# LV8731.net
KiCad netlist of a schematic drawn in Altium Designer
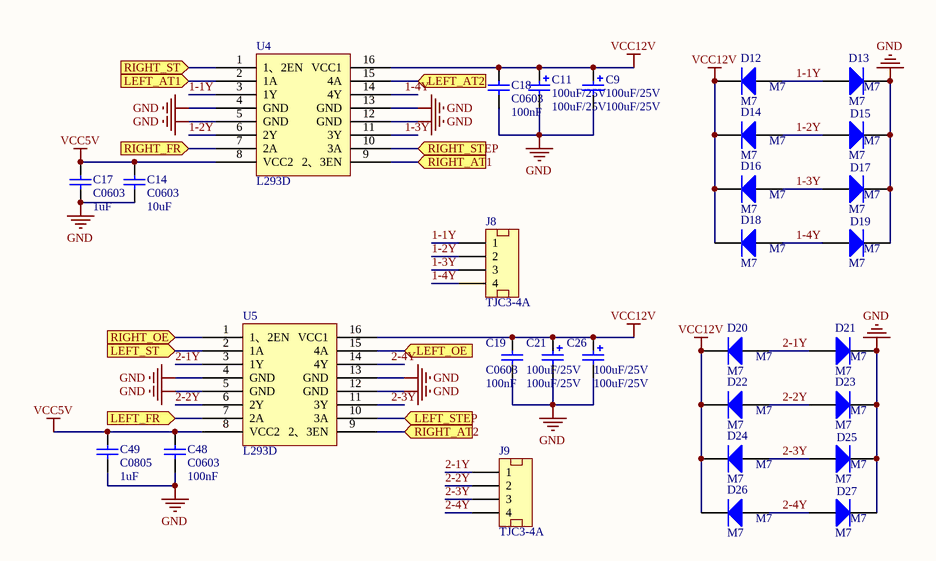
[diagram p0: LV8731.SchDoc]

(export (version "E")
  (design (tool "Eeschema 10.0.6"))
  (components
    (comp (ref "C9")
      (value "100uF/25V")
      (footprint "16V220uF")
      (description "Polarized Capacitor (Surface Mount)")
      (fields (field (name "ALTIUM_VALUE") "100uF/25V"))
      (libsource (lib "schumyhao's_Device") (part "Cap Pol3"))
    )
    (comp (ref "C11")
      (value "100uF/25V")
      (footprint "16V220uF")
      (description "Polarized Capacitor (Surface Mount)")
      (fields (field (name "ALTIUM_VALUE") "100uF/25V"))
      (libsource (lib "schumyhao's_Device") (part "Cap Pol3"))
    )
    (comp (ref "C14")
      (value "C0603")
      (footprint "C0603")
      (description "Capacitor (Semiconductor SIM Model)")
      (fields (field (name "ALTIUM_VALUE") "10uF"))
      (libsource (lib "schumyhao's_Device") (part "Cap Semi"))
    )
    (comp (ref "C17")
      (value "C0603")
      (footprint "C0805")
      (description "Capacitor (Semiconductor SIM Model)")
      (fields (field (name "ALTIUM_VALUE") "1uF"))
      (libsource (lib "schumyhao's_Device") (part "Cap Semi"))
    )
    (comp (ref "C18")
      (value "C0603")
      (footprint "C0603")
      (description "Capacitor (Semiconductor SIM Model)")
      (fields (field (name "ALTIUM_VALUE") "100nF"))
      (libsource (lib "schumyhao's_Device") (part "Cap Semi"))
    )
    (comp (ref "C19")
      (value "C0603")
      (footprint "C0603")
      (description "Capacitor (Semiconductor SIM Model)")
      (fields (field (name "ALTIUM_VALUE") "100nF"))
      (libsource (lib "schumyhao's_Device") (part "Cap Semi"))
    )
    (comp (ref "C21")
      (value "100uF/25V")
      (footprint "16V220uF")
      (description "Polarized Capacitor (Surface Mount)")
      (fields (field (name "ALTIUM_VALUE") "100uF/25V"))
      (libsource (lib "schumyhao's_Device") (part "Cap Pol3"))
    )
    (comp (ref "C26")
      (value "100uF/25V")
      (footprint "16V220uF")
      (description "Polarized Capacitor (Surface Mount)")
      (fields (field (name "ALTIUM_VALUE") "100uF/25V"))
      (libsource (lib "schumyhao's_Device") (part "Cap Pol3"))
    )
    (comp (ref "C48")
      (value "C0603")
      (footprint "C0603")
      (description "Capacitor (Semiconductor SIM Model)")
      (fields (field (name "ALTIUM_VALUE") "100nF"))
      (libsource (lib "schumyhao's_Device") (part "Cap Semi"))
    )
    (comp (ref "C49")
      (value "C0805")
      (footprint "C0805")
      (description "Capacitor (Semiconductor SIM Model)")
      (fields (field (name "ALTIUM_VALUE") "1uF"))
      (libsource (lib "schumyhao's_Device") (part "Cap Semi"))
    )
    (comp (ref "D12")
      (value "M7")
      (footprint "403D_02")
      (description "Default Diode")
      (fields (field (name "ALTIUM_VALUE") "M7") (field (name "PUBLISHER") "Altium Limited"))
      (libsource (lib "Miscellaneous Devices") (part "Diode"))
    )
    (comp (ref "D13")
      (value "M7")
      (footprint "403D_02")
      (description "Default Diode")
      (fields (field (name "ALTIUM_VALUE") "M7") (field (name "PUBLISHER") "Altium Limited"))
      (libsource (lib "Miscellaneous Devices") (part "Diode"))
    )
    (comp (ref "D14")
      (value "M7")
      (footprint "403D_02")
      (description "Default Diode")
      (fields (field (name "ALTIUM_VALUE") "M7") (field (name "PUBLISHER") "Altium Limited"))
      (libsource (lib "Miscellaneous Devices") (part "Diode"))
    )
    (comp (ref "D15")
      (value "M7")
      (footprint "403D_02")
      (description "Default Diode")
      (fields (field (name "ALTIUM_VALUE") "M7") (field (name "PUBLISHER") "Altium Limited"))
      (libsource (lib "Miscellaneous Devices") (part "Diode"))
    )
    (comp (ref "D16")
      (value "M7")
      (footprint "403D_02")
      (description "Default Diode")
      (fields (field (name "ALTIUM_VALUE") "M7") (field (name "PUBLISHER") "Altium Limited"))
      (libsource (lib "Miscellaneous Devices") (part "Diode"))
    )
    (comp (ref "D17")
      (value "M7")
      (footprint "403D_02")
      (description "Default Diode")
      (fields (field (name "ALTIUM_VALUE") "M7") (field (name "PUBLISHER") "Altium Limited"))
      (libsource (lib "Miscellaneous Devices") (part "Diode"))
    )
    (comp (ref "D18")
      (value "M7")
      (footprint "403D_02")
      (description "Default Diode")
      (fields (field (name "ALTIUM_VALUE") "M7") (field (name "PUBLISHER") "Altium Limited"))
      (libsource (lib "Miscellaneous Devices") (part "Diode"))
    )
    (comp (ref "D19")
      (value "M7")
      (footprint "403D_02")
      (description "Default Diode")
      (fields (field (name "ALTIUM_VALUE") "M7") (field (name "PUBLISHER") "Altium Limited"))
      (libsource (lib "Miscellaneous Devices") (part "Diode"))
    )
    (comp (ref "D20")
      (value "M7")
      (footprint "403D_02")
      (description "Default Diode")
      (fields (field (name "ALTIUM_VALUE") "M7") (field (name "PUBLISHER") "Altium Limited"))
      (libsource (lib "Miscellaneous Devices") (part "Diode"))
    )
    (comp (ref "D21")
      (value "M7")
      (footprint "403D_02")
      (description "Default Diode")
      (fields (field (name "ALTIUM_VALUE") "M7") (field (name "PUBLISHER") "Altium Limited"))
      (libsource (lib "Miscellaneous Devices") (part "Diode"))
    )
    (comp (ref "D22")
      (value "M7")
      (footprint "403D_02")
      (description "Default Diode")
      (fields (field (name "ALTIUM_VALUE") "M7") (field (name "PUBLISHER") "Altium Limited"))
      (libsource (lib "Miscellaneous Devices") (part "Diode"))
    )
    (comp (ref "D23")
      (value "M7")
      (footprint "403D_02")
      (description "Default Diode")
      (fields (field (name "ALTIUM_VALUE") "M7") (field (name "PUBLISHER") "Altium Limited"))
      (libsource (lib "Miscellaneous Devices") (part "Diode"))
    )
    (comp (ref "D24")
      (value "M7")
      (footprint "403D_02")
      (description "Default Diode")
      (fields (field (name "ALTIUM_VALUE") "M7") (field (name "PUBLISHER") "Altium Limited"))
      (libsource (lib "Miscellaneous Devices") (part "Diode"))
    )
    (comp (ref "D25")
      (value "M7")
      (footprint "403D_02")
      (description "Default Diode")
      (fields (field (name "ALTIUM_VALUE") "M7") (field (name "PUBLISHER") "Altium Limited"))
      (libsource (lib "Miscellaneous Devices") (part "Diode"))
    )
    (comp (ref "D26")
      (value "M7")
      (footprint "403D_02")
      (description "Default Diode")
      (fields (field (name "ALTIUM_VALUE") "M7") (field (name "PUBLISHER") "Altium Limited"))
      (libsource (lib "Miscellaneous Devices") (part "Diode"))
    )
    (comp (ref "D27")
      (value "M7")
      (footprint "403D_02")
      (description "Default Diode")
      (fields (field (name "ALTIUM_VALUE") "M7") (field (name "PUBLISHER") "Altium Limited"))
      (libsource (lib "Miscellaneous Devices") (part "Diode"))
    )
    (comp (ref "J8")
      (value "TJC3-4A")
      (footprint "TJC3-4A")
      (fields (field (name "PUBLISHER") "Altium Limited"))
      (libsource (lib "schumyhao's_Device") (part "TJC3-4A"))
    )
    (comp (ref "J9")
      (value "TJC3-4A")
      (footprint "TJC3-4A")
      (fields (field (name "PUBLISHER") "Altium Limited"))
      (libsource (lib "schumyhao's_Device") (part "TJC3-4A"))
    )
    (comp (ref "U4") (value "L293D") (footprint "DIP16") (libsource (lib "schumyhao's_IC") (part "L293D")))
    (comp (ref "U5") (value "L293D") (footprint "DIP16") (libsource (lib "schumyhao's_IC") (part "L293D")))
  )
  (nets
    (net (code "1") (name "/1-1Y") (class "Default")
      (node (ref "D12") (pin "1") (pinfunction "A_1") (pintype "passive"))
      (node (ref "D13") (pin "1") (pinfunction "A_1") (pintype "passive"))
      (node (ref "J8") (pin "1") (pinfunction "1_1") (pintype "passive"))
      (node (ref "U4") (pin "3") (pinfunction "1Y_3") (pintype "passive"))
    )
    (net (code "2") (name "/1-2Y") (class "Default")
      (node (ref "D14") (pin "1") (pinfunction "A_1") (pintype "passive"))
      (node (ref "D15") (pin "1") (pinfunction "A_1") (pintype "passive"))
      (node (ref "J8") (pin "2") (pinfunction "2_2") (pintype "passive"))
      (node (ref "U4") (pin "6") (pinfunction "2Y_6") (pintype "passive"))
    )
    (net (code "3") (name "/1-3Y") (class "Default")
      (node (ref "D16") (pin "1") (pinfunction "A_1") (pintype "passive"))
      (node (ref "D17") (pin "1") (pinfunction "A_1") (pintype "passive"))
      (node (ref "J8") (pin "3") (pinfunction "3_3") (pintype "passive"))
      (node (ref "U4") (pin "11") (pinfunction "3Y_11") (pintype "passive"))
    )
    (net (code "4") (name "/1-4Y") (class "Default")
      (node (ref "D18") (pin "1") (pinfunction "A_1") (pintype "passive"))
      (node (ref "D19") (pin "1") (pinfunction "A_1") (pintype "passive"))
      (node (ref "J8") (pin "4") (pinfunction "4_4") (pintype "passive"))
      (node (ref "U4") (pin "14") (pinfunction "4Y_14") (pintype "passive"))
    )
    (net (code "5") (name "/2-1Y") (class "Default")
      (node (ref "D20") (pin "1") (pinfunction "A_1") (pintype "passive"))
      (node (ref "D21") (pin "1") (pinfunction "A_1") (pintype "passive"))
      (node (ref "J9") (pin "1") (pinfunction "1_1") (pintype "passive"))
      (node (ref "U5") (pin "3") (pinfunction "1Y_3") (pintype "passive"))
    )
    (net (code "6") (name "/2-2Y") (class "Default")
      (node (ref "D22") (pin "1") (pinfunction "A_1") (pintype "passive"))
      (node (ref "D23") (pin "1") (pinfunction "A_1") (pintype "passive"))
      (node (ref "J9") (pin "2") (pinfunction "2_2") (pintype "passive"))
      (node (ref "U5") (pin "6") (pinfunction "2Y_6") (pintype "passive"))
    )
    (net (code "7") (name "/2-3Y") (class "Default")
      (node (ref "D24") (pin "1") (pinfunction "A_1") (pintype "passive"))
      (node (ref "D25") (pin "1") (pinfunction "A_1") (pintype "passive"))
      (node (ref "J9") (pin "3") (pinfunction "3_3") (pintype "passive"))
      (node (ref "U5") (pin "11") (pinfunction "3Y_11") (pintype "passive"))
    )
    (net (code "8") (name "/2-4Y") (class "Default")
      (node (ref "D26") (pin "1") (pinfunction "A_1") (pintype "passive"))
      (node (ref "D27") (pin "1") (pinfunction "A_1") (pintype "passive"))
      (node (ref "J9") (pin "4") (pinfunction "4_4") (pintype "passive"))
      (node (ref "U5") (pin "14") (pinfunction "4Y_14") (pintype "passive"))
    )
    (net (code "9") (name "/LEFT_AT1") (class "Default")
      (node (ref "U4") (pin "2") (pinfunction "1A_2") (pintype "passive"))
    )
    (net (code "10") (name "/LEFT_AT2") (class "Default")
      (node (ref "U4") (pin "15") (pinfunction "4A_15") (pintype "passive"))
    )
    (net (code "11") (name "/LEFT_FR") (class "Default")
      (node (ref "U5") (pin "7") (pinfunction "2A_7") (pintype "passive"))
    )
    (net (code "12") (name "/LEFT_OE") (class "Default")
      (node (ref "U5") (pin "15") (pinfunction "4A_15") (pintype "passive"))
    )
    (net (code "13") (name "/LEFT_ST") (class "Default")
      (node (ref "U5") (pin "2") (pinfunction "1A_2") (pintype "passive"))
    )
    (net (code "14") (name "/LEFT_STEP") (class "Default")
      (node (ref "U5") (pin "10") (pinfunction "3A_10") (pintype "passive"))
    )
    (net (code "15") (name "/RIGHT_AT1") (class "Default")
      (node (ref "U4") (pin "9") (pinfunction "2、3EN_9") (pintype "passive"))
    )
    (net (code "16") (name "/RIGHT_AT2") (class "Default")
      (node (ref "U5") (pin "9") (pinfunction "2、3EN_9") (pintype "passive"))
    )
    (net (code "17") (name "/RIGHT_FR") (class "Default")
      (node (ref "U4") (pin "7") (pinfunction "2A_7") (pintype "passive"))
    )
    (net (code "18") (name "/RIGHT_OE") (class "Default")
      (node (ref "U5") (pin "1") (pinfunction "1、2EN_1") (pintype "passive"))
    )
    (net (code "19") (name "/RIGHT_ST") (class "Default")
      (node (ref "U4") (pin "1") (pinfunction "1、2EN_1") (pintype "passive"))
    )
    (net (code "20") (name "/RIGHT_STEP") (class "Default")
      (node (ref "U4") (pin "10") (pinfunction "3A_10") (pintype "passive"))
    )
    (net (code "21") (name "GND") (class "Default")
      (node (ref "C11") (pin "2") (pinfunction "2_2") (pintype "passive"))
      (node (ref "C14") (pin "2") (pinfunction "2_2") (pintype "passive"))
      (node (ref "C17") (pin "1") (pinfunction "1_1") (pintype "passive"))
      (node (ref "C18") (pin "1") (pinfunction "1_1") (pintype "passive"))
      (node (ref "C19") (pin "1") (pinfunction "1_1") (pintype "passive"))
      (node (ref "C21") (pin "2") (pinfunction "2_2") (pintype "passive"))
      (node (ref "C26") (pin "2") (pinfunction "2_2") (pintype "passive"))
      (node (ref "C48") (pin "1") (pinfunction "1_1") (pintype "passive"))
      (node (ref "C49") (pin "1") (pinfunction "1_1") (pintype "passive"))
      (node (ref "C9") (pin "2") (pinfunction "2_2") (pintype "passive"))
      (node (ref "D13") (pin "2") (pinfunction "K_2") (pintype "passive"))
      (node (ref "D15") (pin "2") (pinfunction "K_2") (pintype "passive"))
      (node (ref "D17") (pin "2") (pinfunction "K_2") (pintype "passive"))
      (node (ref "D19") (pin "2") (pinfunction "K_2") (pintype "passive"))
      (node (ref "D21") (pin "2") (pinfunction "K_2") (pintype "passive"))
      (node (ref "D23") (pin "2") (pinfunction "K_2") (pintype "passive"))
      (node (ref "D25") (pin "2") (pinfunction "K_2") (pintype "passive"))
      (node (ref "D27") (pin "2") (pinfunction "K_2") (pintype "passive"))
      (node (ref "U4") (pin "12") (pinfunction "GND_12") (pintype "passive"))
      (node (ref "U4") (pin "13") (pinfunction "GND_13") (pintype "passive"))
      (node (ref "U4") (pin "4") (pinfunction "GND_4") (pintype "passive"))
      (node (ref "U4") (pin "5") (pinfunction "GND_5") (pintype "passive"))
      (node (ref "U5") (pin "12") (pinfunction "GND_12") (pintype "passive"))
      (node (ref "U5") (pin "13") (pinfunction "GND_13") (pintype "passive"))
      (node (ref "U5") (pin "4") (pinfunction "GND_4") (pintype "passive"))
      (node (ref "U5") (pin "5") (pinfunction "GND_5") (pintype "passive"))
    )
    (net (code "22") (name "VCC5V") (class "Default")
      (node (ref "C14") (pin "1") (pinfunction "1_1") (pintype "passive"))
      (node (ref "C17") (pin "2") (pinfunction "2_2") (pintype "passive"))
      (node (ref "C48") (pin "2") (pinfunction "2_2") (pintype "passive"))
      (node (ref "C49") (pin "2") (pinfunction "2_2") (pintype "passive"))
      (node (ref "U4") (pin "8") (pinfunction "VCC2_8") (pintype "passive"))
      (node (ref "U5") (pin "8") (pinfunction "VCC2_8") (pintype "passive"))
    )
    (net (code "23") (name "VCC12V") (class "Default")
      (node (ref "C11") (pin "1") (pinfunction "1_1") (pintype "passive"))
      (node (ref "C18") (pin "2") (pinfunction "2_2") (pintype "passive"))
      (node (ref "C19") (pin "2") (pinfunction "2_2") (pintype "passive"))
      (node (ref "C21") (pin "1") (pinfunction "1_1") (pintype "passive"))
      (node (ref "C26") (pin "1") (pinfunction "1_1") (pintype "passive"))
      (node (ref "C9") (pin "1") (pinfunction "1_1") (pintype "passive"))
      (node (ref "D12") (pin "2") (pinfunction "K_2") (pintype "passive"))
      (node (ref "D14") (pin "2") (pinfunction "K_2") (pintype "passive"))
      (node (ref "D16") (pin "2") (pinfunction "K_2") (pintype "passive"))
      (node (ref "D18") (pin "2") (pinfunction "K_2") (pintype "passive"))
      (node (ref "D20") (pin "2") (pinfunction "K_2") (pintype "passive"))
      (node (ref "D22") (pin "2") (pinfunction "K_2") (pintype "passive"))
      (node (ref "D24") (pin "2") (pinfunction "K_2") (pintype "passive"))
      (node (ref "D26") (pin "2") (pinfunction "K_2") (pintype "passive"))
      (node (ref "U4") (pin "16") (pinfunction "VCC1_16") (pintype "passive"))
      (node (ref "U5") (pin "16") (pinfunction "VCC1_16") (pintype "passive"))
    )
  )
)
